# pc-bus.net
KiCad netlist of a schematic drawn in EAGLE
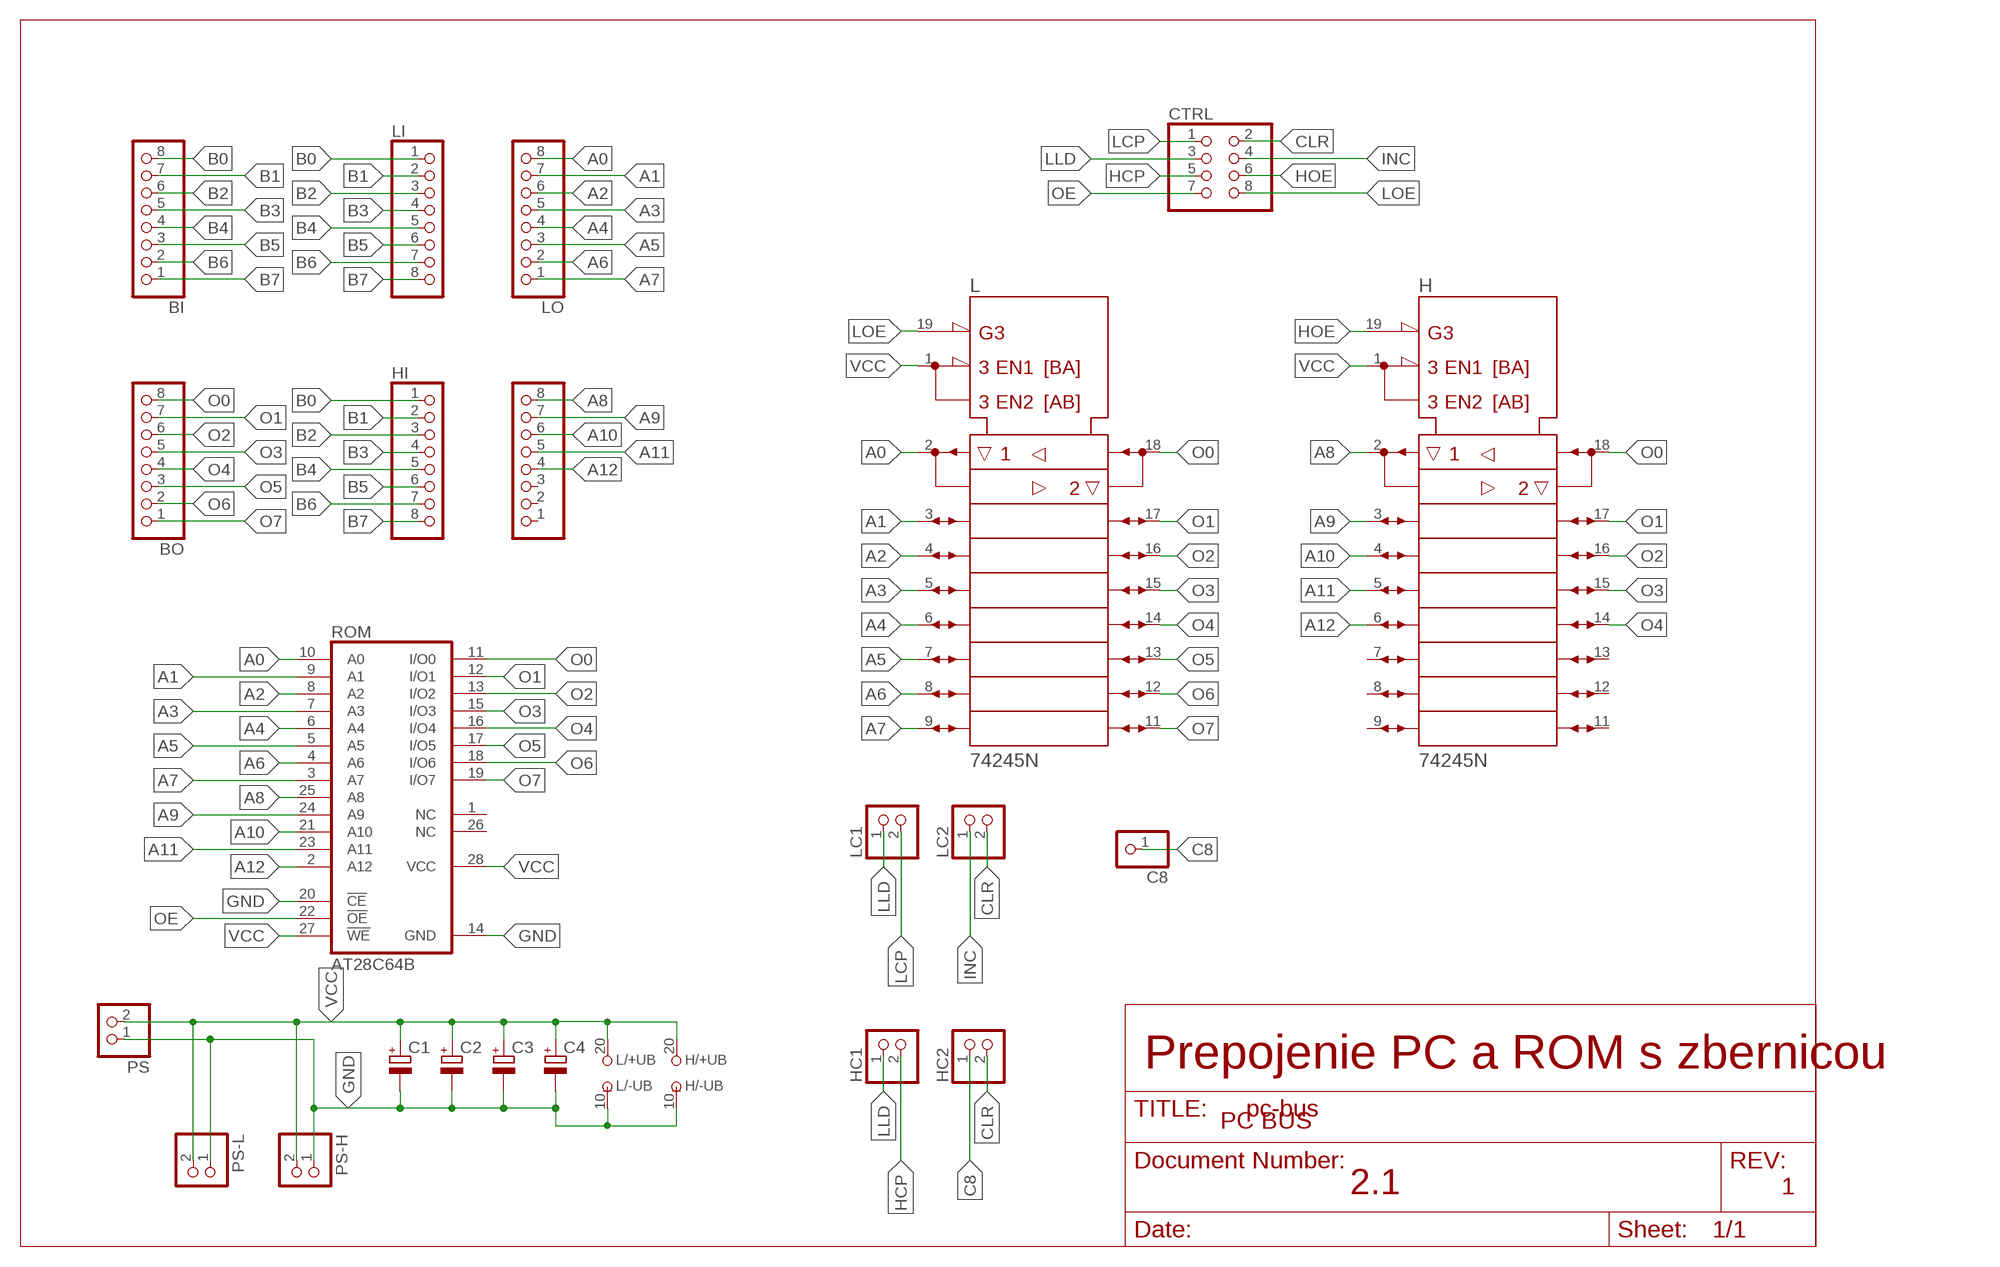
[diagram p0: schematic, sheet 1]

(export (version "E")
  (design (tool "Eeschema 10.0.6"))
  (components
    (comp (ref "BI")
      (value "PINHD-1X8")
      (footprint "eagle-import:1X08")
      (libsource (lib "eagle-import") (part "PINHD-1X8"))
    )
    (comp (ref "BO")
      (value "PINHD-1X8")
      (footprint "eagle-import:1X08")
      (libsource (lib "eagle-import") (part "PINHD-1X8"))
    )
    (comp (ref "C1")
      (value "CPOL-EUE2.5-6")
      (footprint "eagle-import:E2,5-6")
      (libsource (lib "eagle-import") (part "CPOL-EUE2.5-6"))
    )
    (comp (ref "C2")
      (value "CPOL-EUE2.5-6")
      (footprint "eagle-import:E2,5-6")
      (libsource (lib "eagle-import") (part "CPOL-EUE2.5-6"))
    )
    (comp (ref "C3")
      (value "CPOL-EUE2.5-6")
      (footprint "eagle-import:E2,5-6")
      (libsource (lib "eagle-import") (part "CPOL-EUE2.5-6"))
    )
    (comp (ref "C4")
      (value "CPOL-EUE2.5-6")
      (footprint "eagle-import:E2,5-6")
      (libsource (lib "eagle-import") (part "CPOL-EUE2.5-6"))
    )
    (comp (ref "C8")
      (value "PINHD-1X1")
      (footprint "eagle-import:1X01")
      (libsource (lib "eagle-import") (part "PINHD-1X1"))
    )
    (comp (ref "CTRL")
      (value "PINHD-2X4")
      (footprint "eagle-import:2X04")
      (libsource (lib "eagle-import") (part "PINHD-2X4"))
    )
    (comp (ref "H")
      (value "74245N")
      (footprint "eagle-import:DIL20")
      (libsource (lib "eagle-import") (part "74245N"))
    )
    (comp (ref "HC1")
      (value "PINHD-1X2")
      (footprint "eagle-import:1X02")
      (libsource (lib "eagle-import") (part "PINHD-1X2"))
    )
    (comp (ref "HC2")
      (value "PINHD-1X2")
      (footprint "eagle-import:1X02")
      (libsource (lib "eagle-import") (part "PINHD-1X2"))
    )
    (comp (ref "HI")
      (value "PINHD-1X8")
      (footprint "eagle-import:1X08")
      (libsource (lib "eagle-import") (part "PINHD-1X8"))
    )
    (comp (ref "HO")
      (value "PINHD-1X8")
      (footprint "eagle-import:1X08")
      (libsource (lib "eagle-import") (part "PINHD-1X8"))
    )
    (comp (ref "L")
      (value "74245N")
      (footprint "eagle-import:DIL20")
      (libsource (lib "eagle-import") (part "74245N"))
    )
    (comp (ref "LC1")
      (value "PINHD-1X2")
      (footprint "eagle-import:1X02")
      (libsource (lib "eagle-import") (part "PINHD-1X2"))
    )
    (comp (ref "LC2")
      (value "PINHD-1X2")
      (footprint "eagle-import:1X02")
      (libsource (lib "eagle-import") (part "PINHD-1X2"))
    )
    (comp (ref "LI")
      (value "PINHD-1X8")
      (footprint "eagle-import:1X08")
      (libsource (lib "eagle-import") (part "PINHD-1X8"))
    )
    (comp (ref "LO")
      (value "PINHD-1X8")
      (footprint "eagle-import:1X08")
      (libsource (lib "eagle-import") (part "PINHD-1X8"))
    )
    (comp (ref "PS")
      (value "PINHD-1X2")
      (footprint "eagle-import:1X02")
      (libsource (lib "eagle-import") (part "PINHD-1X2"))
    )
    (comp (ref "PS-H")
      (value "PINHD-1X2")
      (footprint "eagle-import:1X02")
      (libsource (lib "eagle-import") (part "PINHD-1X2"))
    )
    (comp (ref "PS-L")
      (value "PINHD-1X2")
      (footprint "eagle-import:1X02")
      (libsource (lib "eagle-import") (part "PINHD-1X2"))
    )
    (comp (ref "ROM")
      (value "AT28C64B")
      (footprint "eagle-import:DIL28-6")
      (fields (field (name "MPN") "AT28C64B-15PU"))
      (libsource (lib "eagle-import") (part "28C64C"))
    )
  )
  (nets
    (net (code "1") (name "A0") (class "Default")
      (node (ref "L") (pin "2") (pinfunction "A1_2") (pintype "bidirectional"))
      (node (ref "LO") (pin "8") (pinfunction "8_8") (pintype "passive"))
      (node (ref "ROM") (pin "10") (pinfunction "A0_10") (pintype "input"))
    )
    (net (code "2") (name "A1") (class "Default")
      (node (ref "L") (pin "3") (pinfunction "A2_3") (pintype "bidirectional"))
      (node (ref "LO") (pin "7") (pinfunction "7_7") (pintype "passive"))
      (node (ref "ROM") (pin "9") (pinfunction "A1_9") (pintype "input"))
    )
    (net (code "3") (name "A2") (class "Default")
      (node (ref "L") (pin "4") (pinfunction "A3_4") (pintype "bidirectional"))
      (node (ref "LO") (pin "6") (pinfunction "6_6") (pintype "passive"))
      (node (ref "ROM") (pin "8") (pinfunction "A2_8") (pintype "input"))
    )
    (net (code "4") (name "A3") (class "Default")
      (node (ref "L") (pin "5") (pinfunction "A4_5") (pintype "bidirectional"))
      (node (ref "LO") (pin "5") (pinfunction "5_5") (pintype "passive"))
      (node (ref "ROM") (pin "7") (pinfunction "A3_7") (pintype "input"))
    )
    (net (code "5") (name "A4") (class "Default")
      (node (ref "L") (pin "6") (pinfunction "A5_6") (pintype "bidirectional"))
      (node (ref "LO") (pin "4") (pinfunction "4_4") (pintype "passive"))
      (node (ref "ROM") (pin "6") (pinfunction "A4_6") (pintype "input"))
    )
    (net (code "6") (name "A5") (class "Default")
      (node (ref "L") (pin "7") (pinfunction "A6_7") (pintype "bidirectional"))
      (node (ref "LO") (pin "3") (pinfunction "3_3") (pintype "passive"))
      (node (ref "ROM") (pin "5") (pinfunction "A5_5") (pintype "input"))
    )
    (net (code "7") (name "A6") (class "Default")
      (node (ref "L") (pin "8") (pinfunction "A7_8") (pintype "bidirectional"))
      (node (ref "LO") (pin "2") (pinfunction "2_2") (pintype "passive"))
      (node (ref "ROM") (pin "4") (pinfunction "A6_4") (pintype "input"))
    )
    (net (code "8") (name "A7") (class "Default")
      (node (ref "L") (pin "9") (pinfunction "A8_9") (pintype "bidirectional"))
      (node (ref "LO") (pin "1") (pinfunction "1_1") (pintype "passive"))
      (node (ref "ROM") (pin "3") (pinfunction "A7_3") (pintype "input"))
    )
    (net (code "9") (name "A8") (class "Default")
      (node (ref "H") (pin "2") (pinfunction "A1_2") (pintype "bidirectional"))
      (node (ref "HO") (pin "8") (pinfunction "8_8") (pintype "passive"))
      (node (ref "ROM") (pin "25") (pinfunction "A8_25") (pintype "input"))
    )
    (net (code "10") (name "A9") (class "Default")
      (node (ref "H") (pin "3") (pinfunction "A2_3") (pintype "bidirectional"))
      (node (ref "HO") (pin "7") (pinfunction "7_7") (pintype "passive"))
      (node (ref "ROM") (pin "24") (pinfunction "A9_24") (pintype "input"))
    )
    (net (code "11") (name "A10") (class "Default")
      (node (ref "H") (pin "4") (pinfunction "A3_4") (pintype "bidirectional"))
      (node (ref "HO") (pin "6") (pinfunction "6_6") (pintype "passive"))
      (node (ref "ROM") (pin "21") (pinfunction "A10_21") (pintype "input"))
    )
    (net (code "12") (name "A11") (class "Default")
      (node (ref "H") (pin "5") (pinfunction "A4_5") (pintype "bidirectional"))
      (node (ref "HO") (pin "5") (pinfunction "5_5") (pintype "passive"))
      (node (ref "ROM") (pin "23") (pinfunction "A11_23") (pintype "input"))
    )
    (net (code "13") (name "A12") (class "Default")
      (node (ref "H") (pin "6") (pinfunction "A5_6") (pintype "bidirectional"))
      (node (ref "HO") (pin "4") (pinfunction "4_4") (pintype "passive"))
      (node (ref "ROM") (pin "2") (pinfunction "A12_2") (pintype "input"))
    )
    (net (code "14") (name "B0") (class "Default")
      (node (ref "BI") (pin "8") (pinfunction "8_8") (pintype "passive"))
      (node (ref "HI") (pin "1") (pinfunction "1_1") (pintype "passive"))
      (node (ref "LI") (pin "1") (pinfunction "1_1") (pintype "passive"))
    )
    (net (code "15") (name "B1") (class "Default")
      (node (ref "BI") (pin "7") (pinfunction "7_7") (pintype "passive"))
      (node (ref "HI") (pin "2") (pinfunction "2_2") (pintype "passive"))
      (node (ref "LI") (pin "2") (pinfunction "2_2") (pintype "passive"))
    )
    (net (code "16") (name "B2") (class "Default")
      (node (ref "BI") (pin "6") (pinfunction "6_6") (pintype "passive"))
      (node (ref "HI") (pin "3") (pinfunction "3_3") (pintype "passive"))
      (node (ref "LI") (pin "3") (pinfunction "3_3") (pintype "passive"))
    )
    (net (code "17") (name "B3") (class "Default")
      (node (ref "BI") (pin "5") (pinfunction "5_5") (pintype "passive"))
      (node (ref "HI") (pin "4") (pinfunction "4_4") (pintype "passive"))
      (node (ref "LI") (pin "4") (pinfunction "4_4") (pintype "passive"))
    )
    (net (code "18") (name "B4") (class "Default")
      (node (ref "BI") (pin "4") (pinfunction "4_4") (pintype "passive"))
      (node (ref "HI") (pin "5") (pinfunction "5_5") (pintype "passive"))
      (node (ref "LI") (pin "5") (pinfunction "5_5") (pintype "passive"))
    )
    (net (code "19") (name "B5") (class "Default")
      (node (ref "BI") (pin "3") (pinfunction "3_3") (pintype "passive"))
      (node (ref "HI") (pin "6") (pinfunction "6_6") (pintype "passive"))
      (node (ref "LI") (pin "6") (pinfunction "6_6") (pintype "passive"))
    )
    (net (code "20") (name "B6") (class "Default")
      (node (ref "BI") (pin "2") (pinfunction "2_2") (pintype "passive"))
      (node (ref "HI") (pin "7") (pinfunction "7_7") (pintype "passive"))
      (node (ref "LI") (pin "7") (pinfunction "7_7") (pintype "passive"))
    )
    (net (code "21") (name "B7") (class "Default")
      (node (ref "BI") (pin "1") (pinfunction "1_1") (pintype "passive"))
      (node (ref "HI") (pin "8") (pinfunction "8_8") (pintype "passive"))
      (node (ref "LI") (pin "8") (pinfunction "8_8") (pintype "passive"))
    )
    (net (code "22") (name "C8") (class "Default")
      (node (ref "C8") (pin "1") (pinfunction "1_1") (pintype "passive"))
      (node (ref "HC2") (pin "1") (pinfunction "1_1") (pintype "passive"))
    )
    (net (code "23") (name "CLR") (class "Default")
      (node (ref "CTRL") (pin "2") (pinfunction "2_2") (pintype "passive"))
      (node (ref "HC2") (pin "2") (pinfunction "2_2") (pintype "passive"))
      (node (ref "LC2") (pin "2") (pinfunction "2_2") (pintype "passive"))
    )
    (net (code "24") (name "GND") (class "Default")
      (node (ref "C1") (pin "-") (pinfunction "-_-") (pintype "passive"))
      (node (ref "C2") (pin "-") (pinfunction "-_-") (pintype "passive"))
      (node (ref "C3") (pin "-") (pinfunction "-_-") (pintype "passive"))
      (node (ref "C4") (pin "-") (pinfunction "-_-") (pintype "passive"))
      (node (ref "H") (pin "10") (pinfunction "-UB_10") (pintype "power_in"))
      (node (ref "L") (pin "10") (pinfunction "-UB_10") (pintype "power_in"))
      (node (ref "PS") (pin "1") (pinfunction "1_1") (pintype "passive"))
      (node (ref "PS-H") (pin "1") (pinfunction "1_1") (pintype "passive"))
      (node (ref "PS-L") (pin "1") (pinfunction "1_1") (pintype "passive"))
      (node (ref "ROM") (pin "14") (pinfunction "GND_14") (pintype "power_in"))
      (node (ref "ROM") (pin "20") (pinfunction "~{CE}_20") (pintype "input"))
    )
    (net (code "25") (name "HCP") (class "Default")
      (node (ref "CTRL") (pin "5") (pinfunction "5_5") (pintype "passive"))
      (node (ref "HC1") (pin "2") (pinfunction "2_2") (pintype "passive"))
    )
    (net (code "26") (name "HOE") (class "Default")
      (node (ref "CTRL") (pin "6") (pinfunction "6_6") (pintype "passive"))
      (node (ref "H") (pin "19") (pinfunction "~{G}_19") (pintype "input"))
    )
    (net (code "27") (name "INC") (class "Default")
      (node (ref "CTRL") (pin "4") (pinfunction "4_4") (pintype "passive"))
      (node (ref "LC2") (pin "1") (pinfunction "1_1") (pintype "passive"))
    )
    (net (code "28") (name "LCP") (class "Default")
      (node (ref "CTRL") (pin "1") (pinfunction "1_1") (pintype "passive"))
      (node (ref "LC1") (pin "2") (pinfunction "2_2") (pintype "passive"))
    )
    (net (code "29") (name "LLD") (class "Default")
      (node (ref "CTRL") (pin "3") (pinfunction "3_3") (pintype "passive"))
      (node (ref "HC1") (pin "1") (pinfunction "1_1") (pintype "passive"))
      (node (ref "LC1") (pin "1") (pinfunction "1_1") (pintype "passive"))
    )
    (net (code "30") (name "LOE") (class "Default")
      (node (ref "CTRL") (pin "8") (pinfunction "8_8") (pintype "passive"))
      (node (ref "L") (pin "19") (pinfunction "~{G}_19") (pintype "input"))
    )
    (net (code "31") (name "O0") (class "Default")
      (node (ref "BO") (pin "8") (pinfunction "8_8") (pintype "passive"))
      (node (ref "H") (pin "18") (pinfunction "B1_18") (pintype "bidirectional"))
      (node (ref "L") (pin "18") (pinfunction "B1_18") (pintype "bidirectional"))
      (node (ref "ROM") (pin "11") (pinfunction "I/O0_11") (pintype "bidirectional"))
    )
    (net (code "32") (name "O1") (class "Default")
      (node (ref "BO") (pin "7") (pinfunction "7_7") (pintype "passive"))
      (node (ref "H") (pin "17") (pinfunction "B2_17") (pintype "bidirectional"))
      (node (ref "L") (pin "17") (pinfunction "B2_17") (pintype "bidirectional"))
      (node (ref "ROM") (pin "12") (pinfunction "I/O1_12") (pintype "bidirectional"))
    )
    (net (code "33") (name "O2") (class "Default")
      (node (ref "BO") (pin "6") (pinfunction "6_6") (pintype "passive"))
      (node (ref "H") (pin "16") (pinfunction "B3_16") (pintype "bidirectional"))
      (node (ref "L") (pin "16") (pinfunction "B3_16") (pintype "bidirectional"))
      (node (ref "ROM") (pin "13") (pinfunction "I/O2_13") (pintype "bidirectional"))
    )
    (net (code "34") (name "O3") (class "Default")
      (node (ref "BO") (pin "5") (pinfunction "5_5") (pintype "passive"))
      (node (ref "H") (pin "15") (pinfunction "B4_15") (pintype "bidirectional"))
      (node (ref "L") (pin "15") (pinfunction "B4_15") (pintype "bidirectional"))
      (node (ref "ROM") (pin "15") (pinfunction "I/O3_15") (pintype "bidirectional"))
    )
    (net (code "35") (name "O4") (class "Default")
      (node (ref "BO") (pin "4") (pinfunction "4_4") (pintype "passive"))
      (node (ref "H") (pin "14") (pinfunction "B5_14") (pintype "bidirectional"))
      (node (ref "L") (pin "14") (pinfunction "B5_14") (pintype "bidirectional"))
      (node (ref "ROM") (pin "16") (pinfunction "I/O4_16") (pintype "bidirectional"))
    )
    (net (code "36") (name "O5") (class "Default")
      (node (ref "BO") (pin "3") (pinfunction "3_3") (pintype "passive"))
      (node (ref "L") (pin "13") (pinfunction "B6_13") (pintype "bidirectional"))
      (node (ref "ROM") (pin "17") (pinfunction "I/O5_17") (pintype "bidirectional"))
    )
    (net (code "37") (name "O6") (class "Default")
      (node (ref "BO") (pin "2") (pinfunction "2_2") (pintype "passive"))
      (node (ref "L") (pin "12") (pinfunction "B7_12") (pintype "bidirectional"))
      (node (ref "ROM") (pin "18") (pinfunction "I/O6_18") (pintype "bidirectional"))
    )
    (net (code "38") (name "O7") (class "Default")
      (node (ref "BO") (pin "1") (pinfunction "1_1") (pintype "passive"))
      (node (ref "L") (pin "11") (pinfunction "B8_11") (pintype "bidirectional"))
      (node (ref "ROM") (pin "19") (pinfunction "I/O7_19") (pintype "bidirectional"))
    )
    (net (code "39") (name "OE") (class "Default")
      (node (ref "CTRL") (pin "7") (pinfunction "7_7") (pintype "passive"))
      (node (ref "ROM") (pin "22") (pinfunction "~{OE}_22") (pintype "input"))
    )
    (net (code "40") (name "VCC") (class "Default")
      (node (ref "C1") (pin "+") (pinfunction "+_+") (pintype "passive"))
      (node (ref "C2") (pin "+") (pinfunction "+_+") (pintype "passive"))
      (node (ref "C3") (pin "+") (pinfunction "+_+") (pintype "passive"))
      (node (ref "C4") (pin "+") (pinfunction "+_+") (pintype "passive"))
      (node (ref "H") (pin "1") (pinfunction "DIR_1") (pintype "input"))
      (node (ref "H") (pin "20") (pinfunction "+UB_20") (pintype "power_in"))
      (node (ref "L") (pin "1") (pinfunction "DIR_1") (pintype "input"))
      (node (ref "L") (pin "20") (pinfunction "+UB_20") (pintype "power_in"))
      (node (ref "PS") (pin "2") (pinfunction "2_2") (pintype "passive"))
      (node (ref "PS-H") (pin "2") (pinfunction "2_2") (pintype "passive"))
      (node (ref "PS-L") (pin "2") (pinfunction "2_2") (pintype "passive"))
      (node (ref "ROM") (pin "27") (pinfunction "~{WE}_27") (pintype "input"))
      (node (ref "ROM") (pin "28") (pinfunction "VCC_28") (pintype "power_in"))
    )
    (net (code "41") (name "unconnected-(HC-A6-Pad7)") (class "Default")
      (node (ref "H") (pin "7") (pinfunction "A6_7") (pintype "bidirectional"))
    )
    (net (code "42") (name "unconnected-(HC-A7-Pad8)") (class "Default")
      (node (ref "H") (pin "8") (pinfunction "A7_8") (pintype "bidirectional"))
    )
    (net (code "43") (name "unconnected-(HC-A8-Pad9)") (class "Default")
      (node (ref "H") (pin "9") (pinfunction "A8_9") (pintype "bidirectional"))
    )
    (net (code "44") (name "unconnected-(HC-B6-Pad13)") (class "Default")
      (node (ref "H") (pin "13") (pinfunction "B6_13") (pintype "bidirectional"))
    )
    (net (code "45") (name "unconnected-(HC-B7-Pad12)") (class "Default")
      (node (ref "H") (pin "12") (pinfunction "B7_12") (pintype "bidirectional"))
    )
    (net (code "46") (name "unconnected-(HC-B8-Pad11)") (class "Default")
      (node (ref "H") (pin "11") (pinfunction "B8_11") (pintype "bidirectional"))
    )
    (net (code "47") (name "unconnected-(HO-Pad1)") (class "Default")
      (node (ref "HO") (pin "1") (pinfunction "1_1") (pintype "passive"))
    )
    (net (code "48") (name "unconnected-(HO-Pad2)") (class "Default")
      (node (ref "HO") (pin "2") (pinfunction "2_2") (pintype "passive"))
    )
    (net (code "49") (name "unconnected-(HO-Pad3)") (class "Default")
      (node (ref "HO") (pin "3") (pinfunction "3_3") (pintype "passive"))
    )
    (net (code "50") (name "unconnected-(ROM-NC-Pad1)") (class "Default")
      (node (ref "ROM") (pin "1") (pinfunction "NC_1") (pintype "no_connect"))
    )
    (net (code "51") (name "unconnected-(ROM-NC-Pad26)") (class "Default")
      (node (ref "ROM") (pin "26") (pinfunction "NC_26") (pintype "no_connect"))
    )
  )
)
